# NAME_of_the_Game__NAND_Circuitry___Op-Am.net
KiCad netlist of a schematic drawn in EAGLE
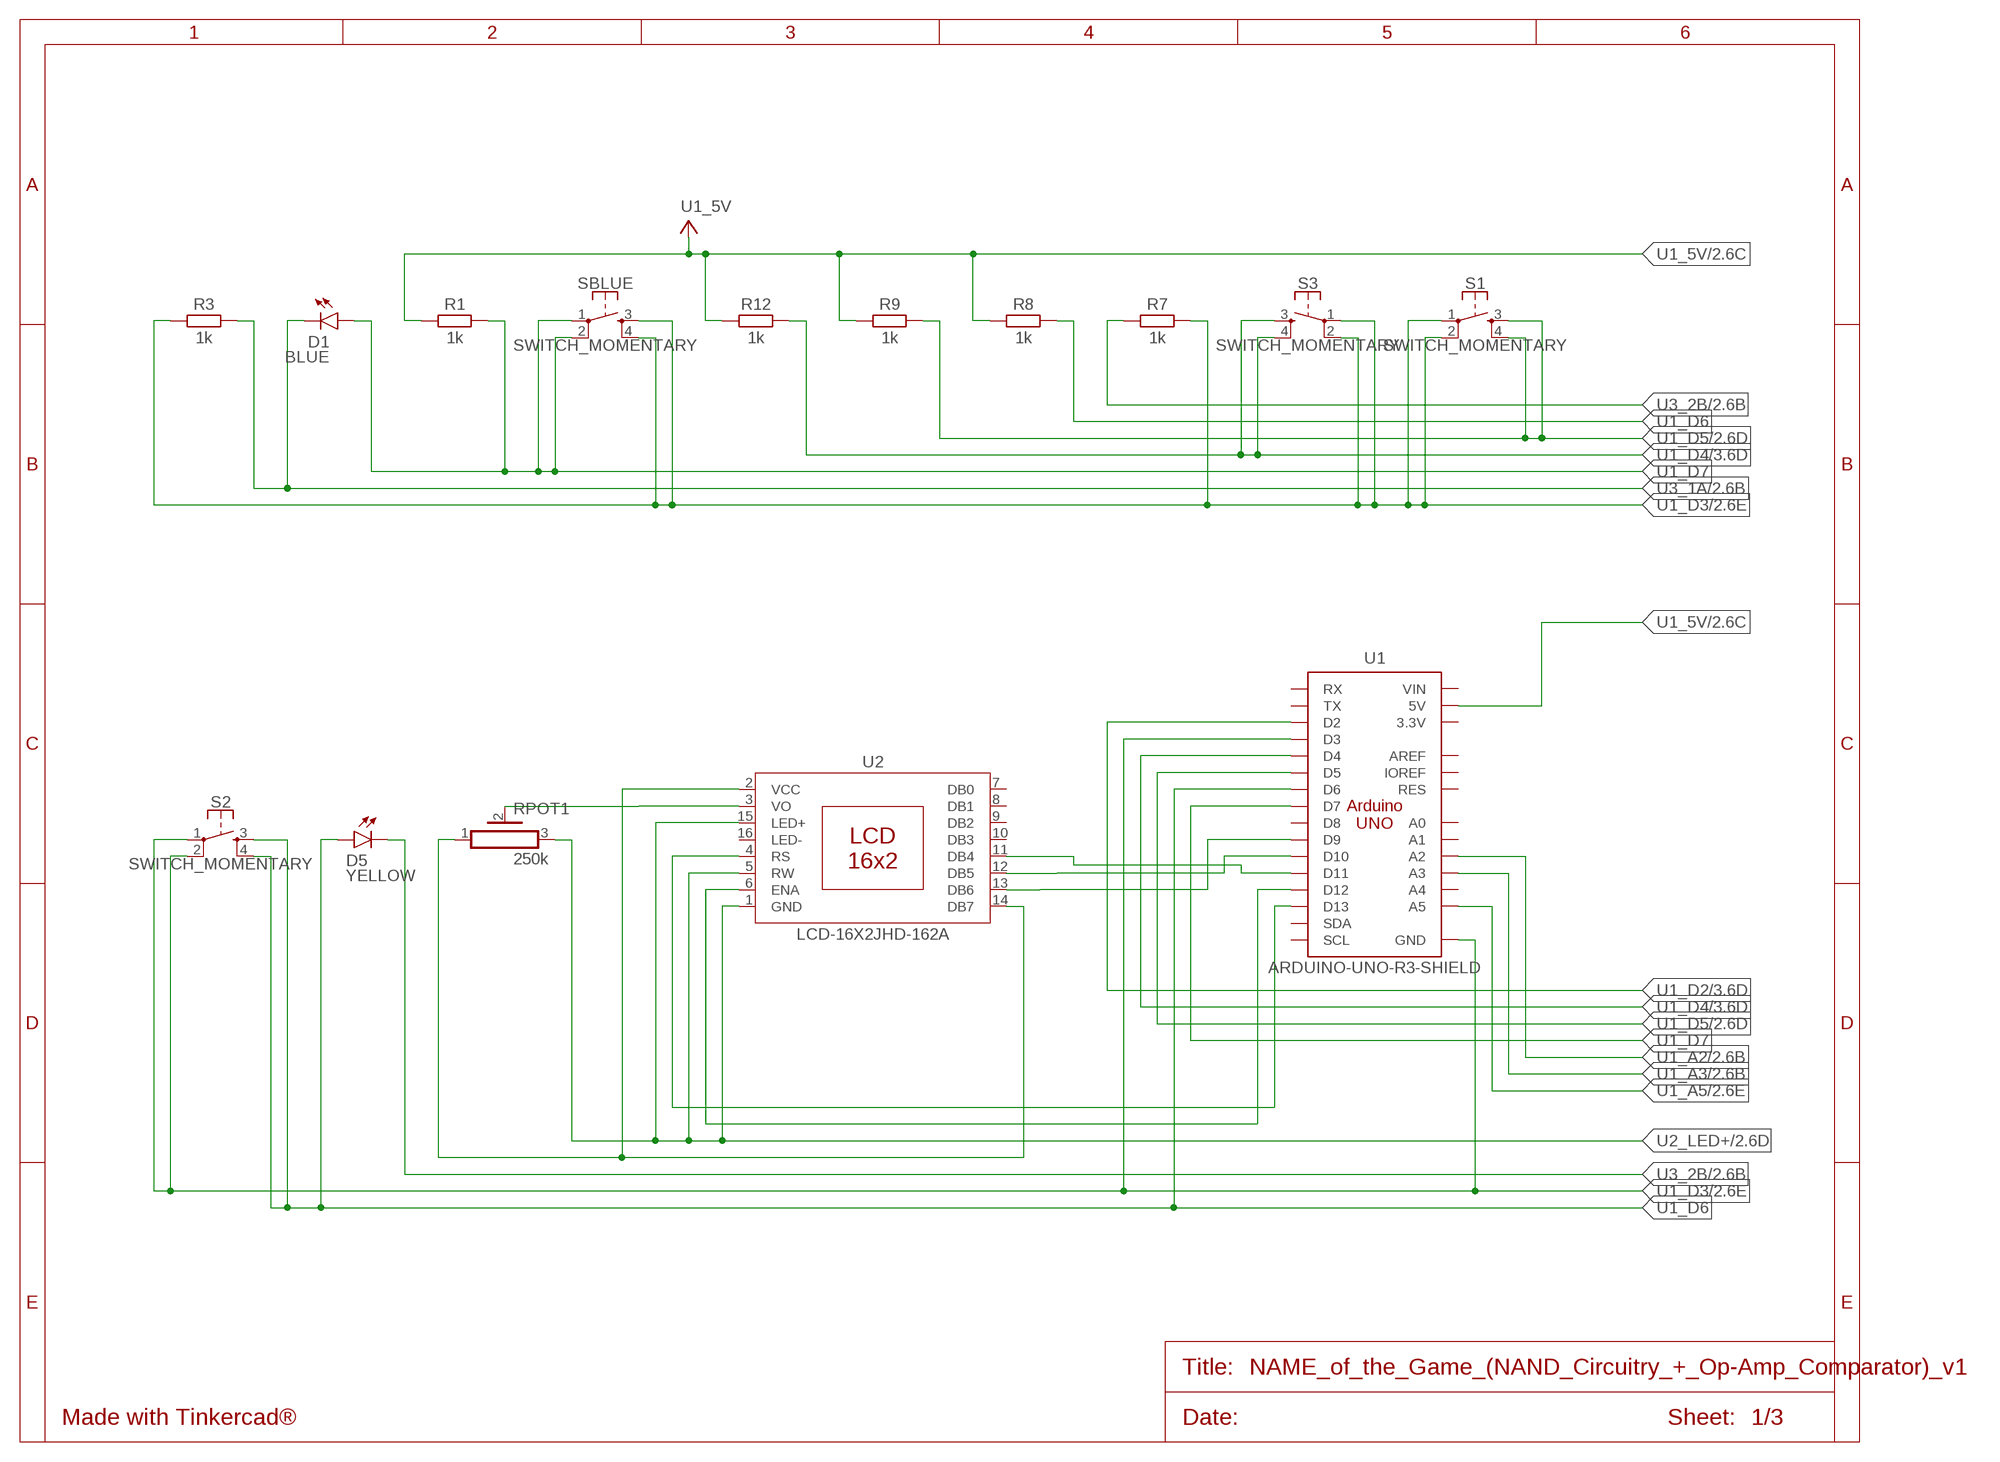
[diagram p0: schematic, sheet 1]
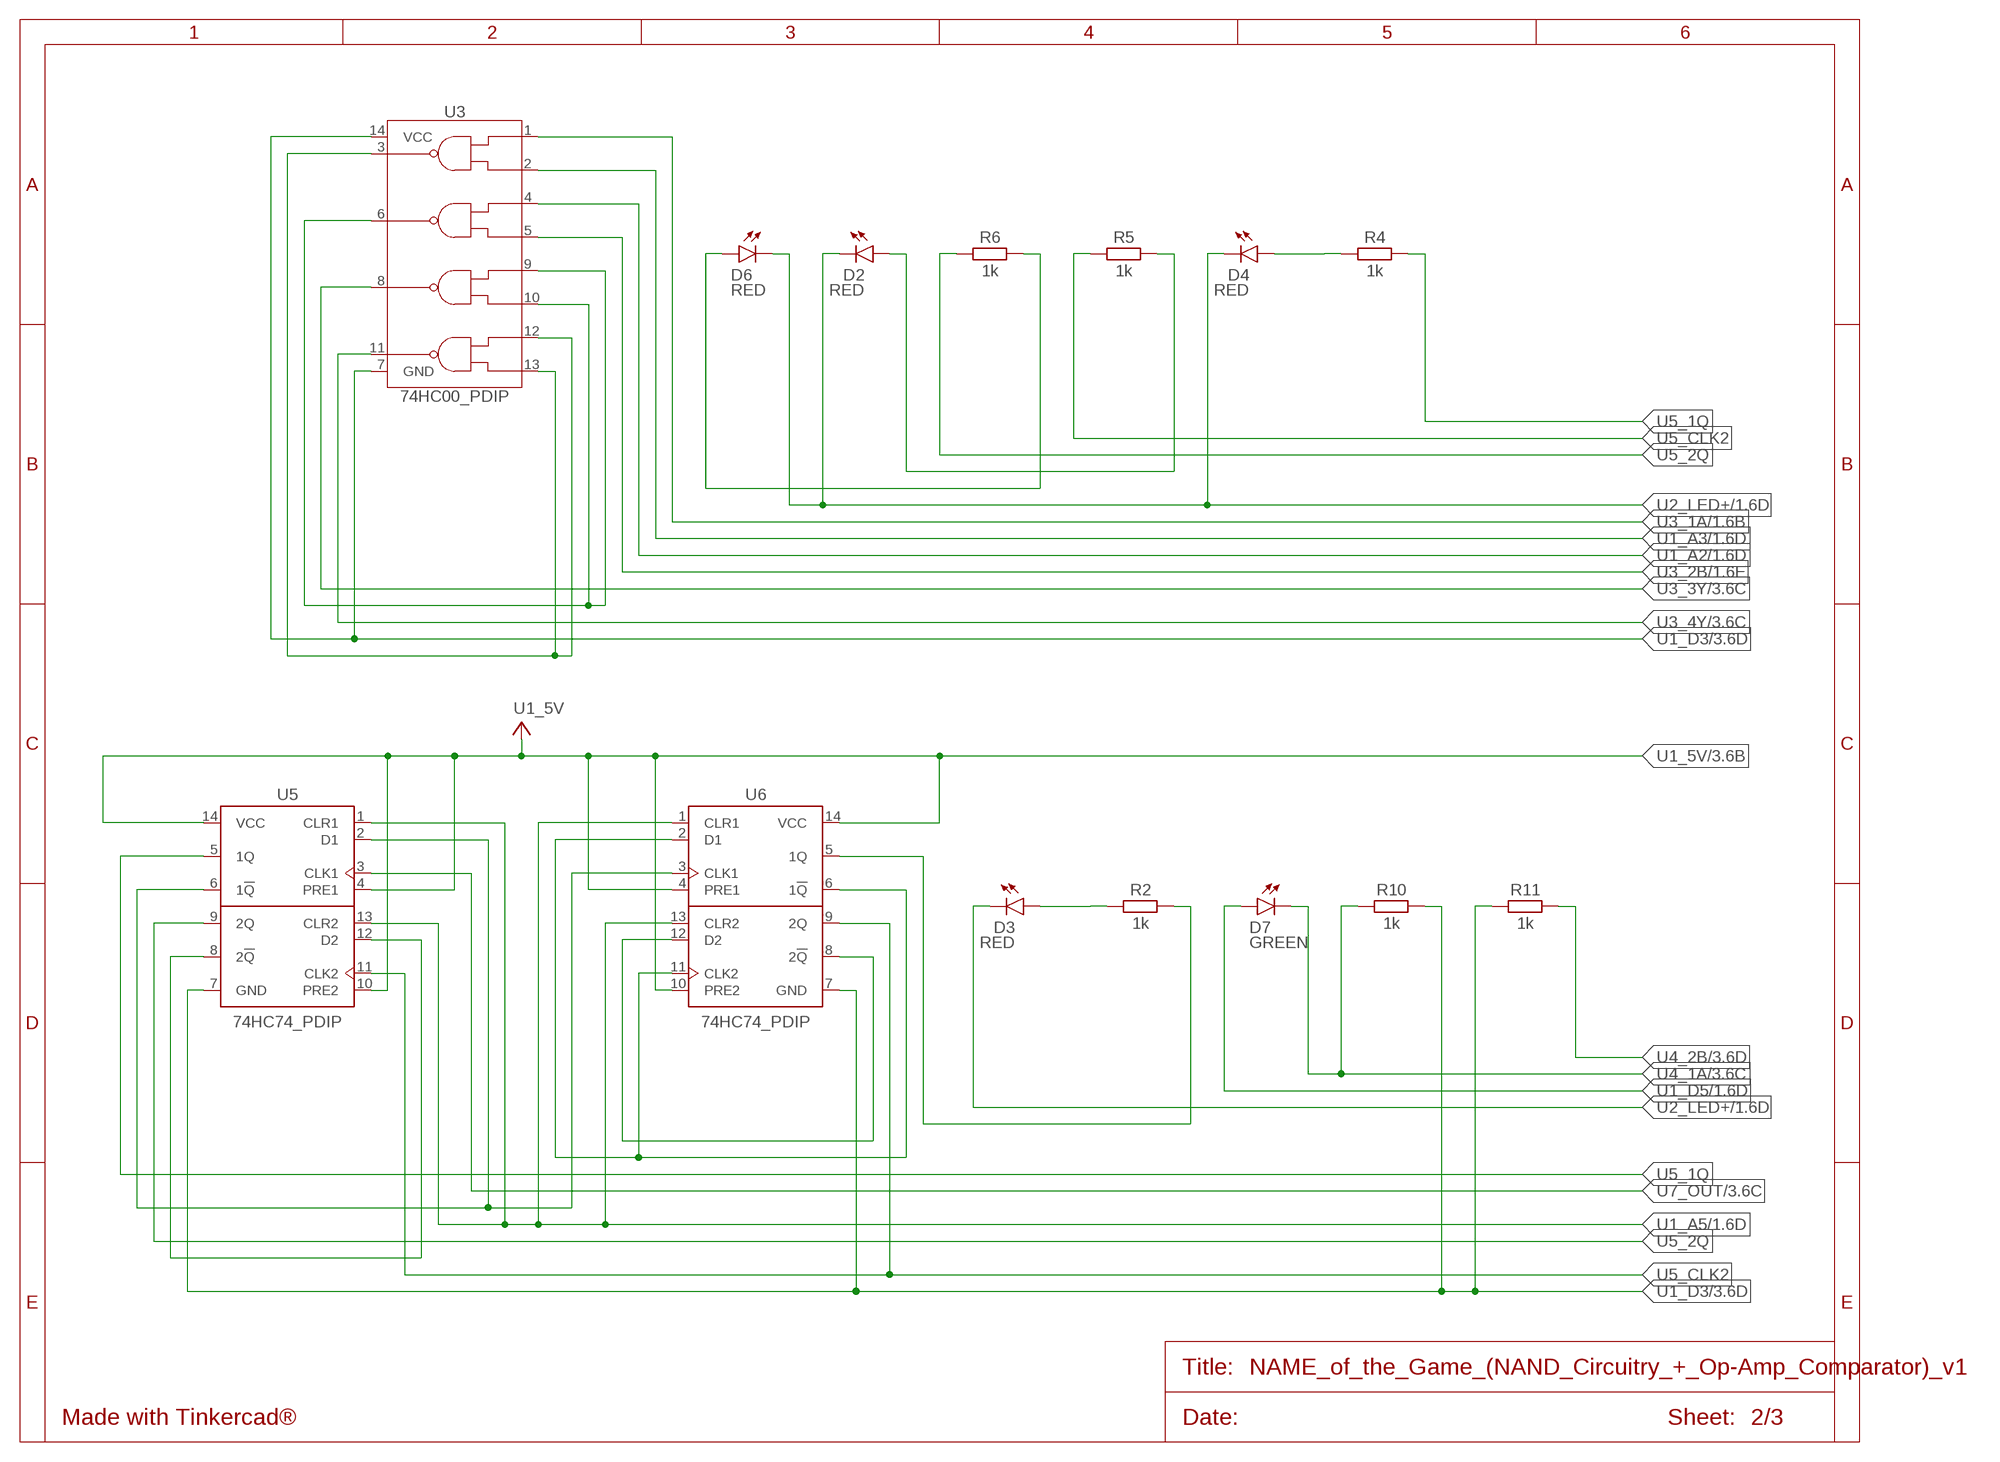
[diagram p1: schematic, sheet 2]
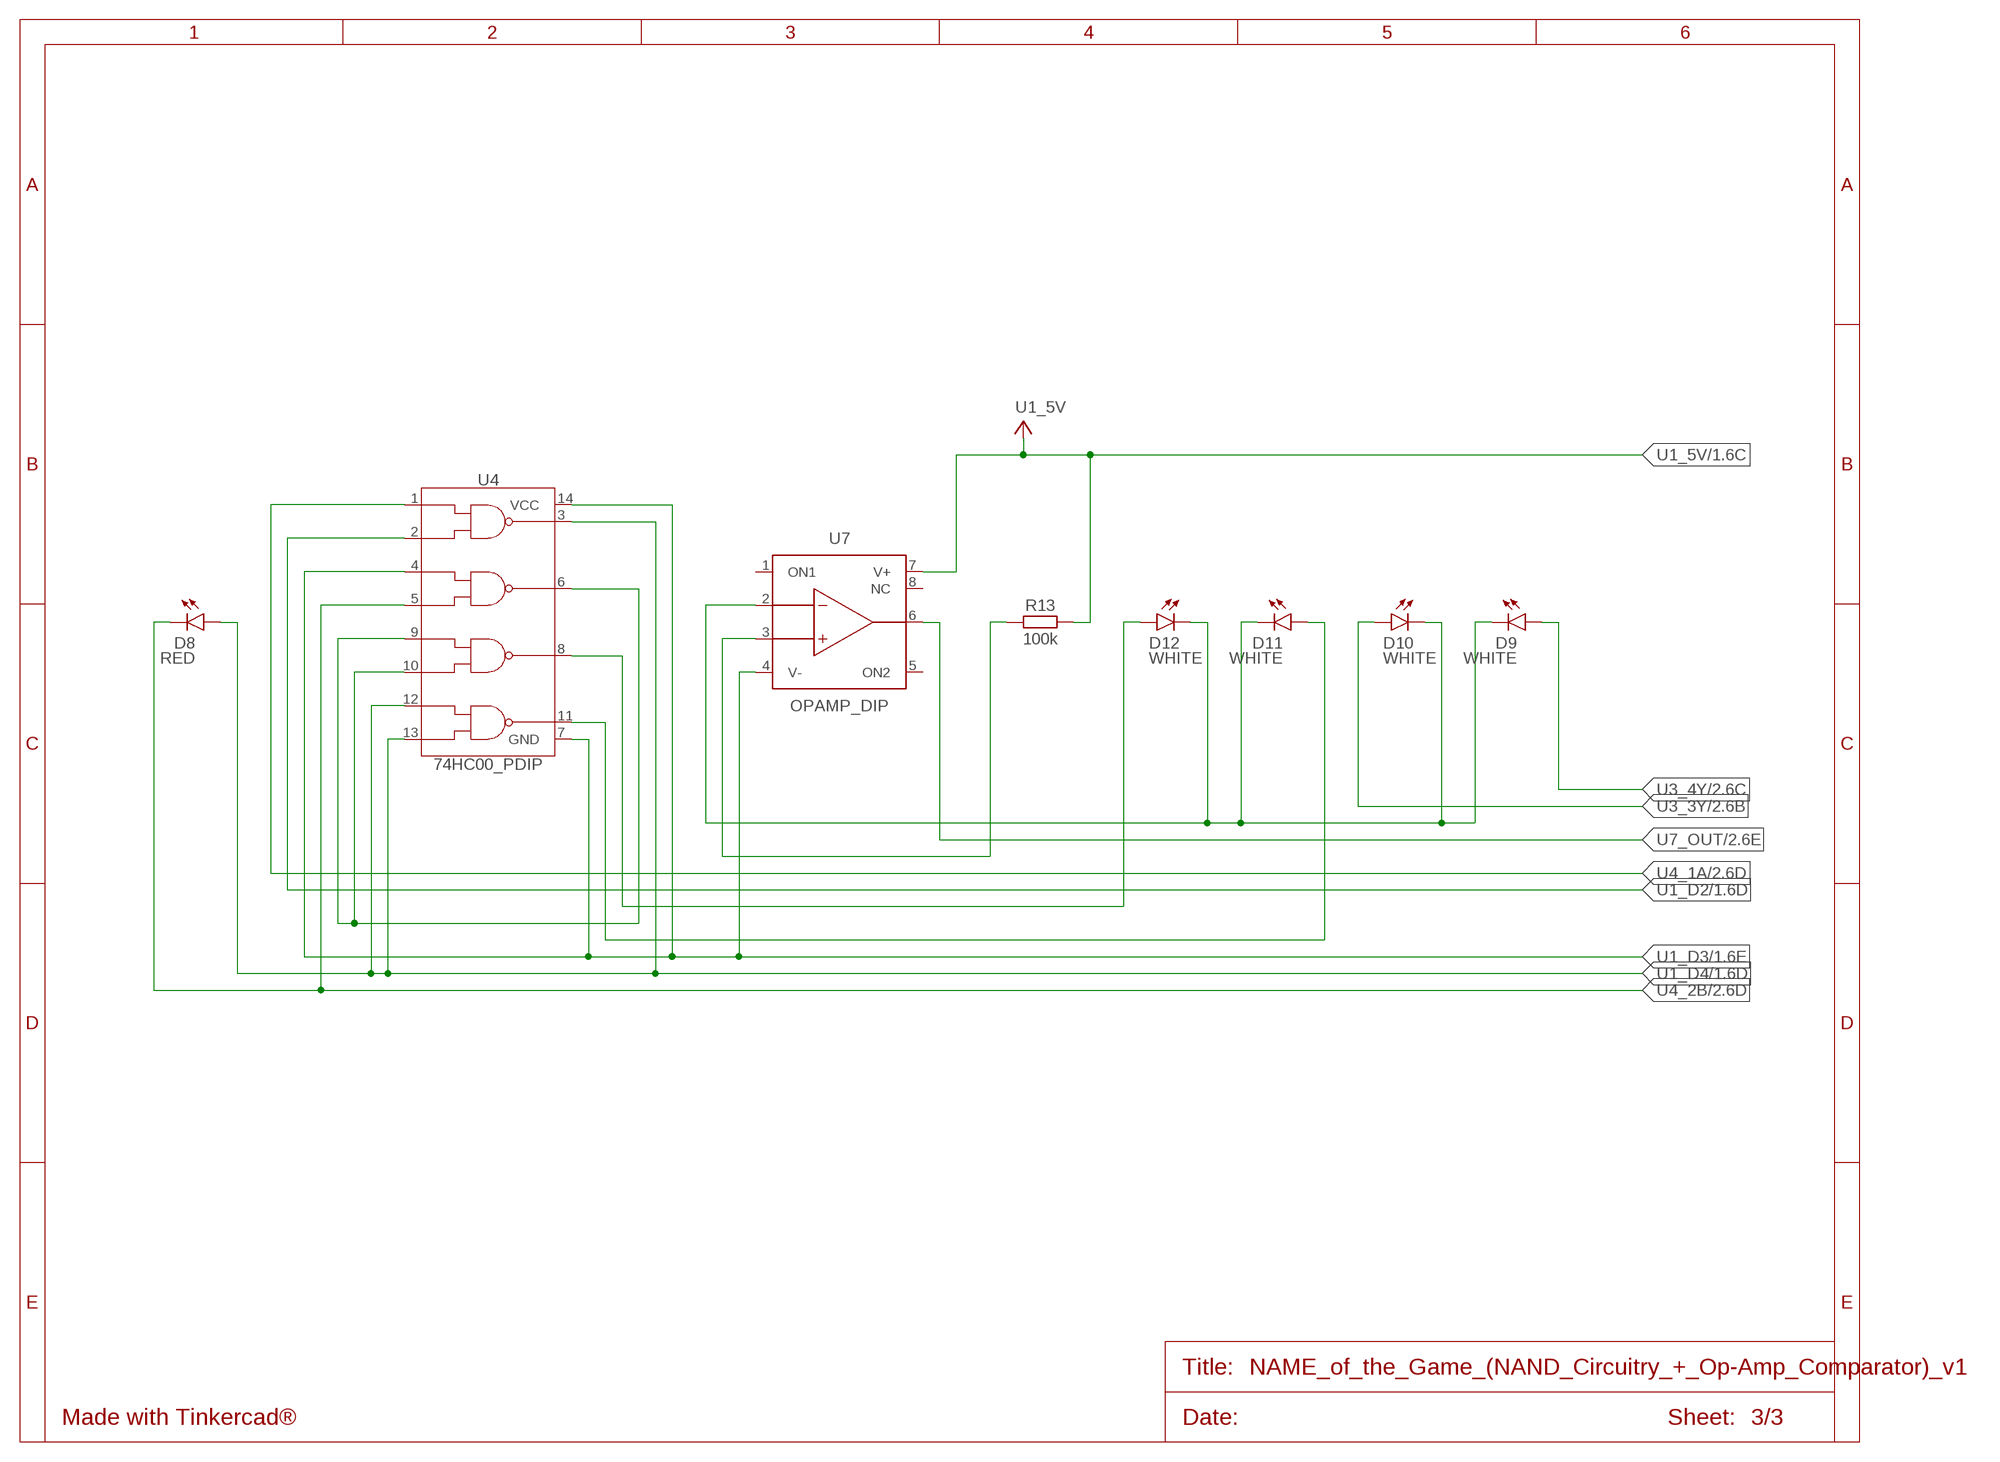
[diagram p2: schematic, sheet 3]

(export (version "E")
  (design (tool "Eeschema 10.0.6"))
  (components
    (comp (ref "D1")
      (value "BLUE")
      (footprint "eagle-import:LEDRD254W60D565H860B_B")
      (libsource (lib "eagle-import") (part "LED_RADIALBLUE_"))
    )
    (comp (ref "D5")
      (value "YELLOW")
      (footprint "eagle-import:LEDRD254W60D565H860B_Y")
      (libsource (lib "eagle-import") (part "LED_RADIALYELLOW_"))
    )
    (comp (ref "R1")
      (value "1k")
      (footprint "eagle-import:RESAD1016W63L850D250B")
      (libsource (lib "eagle-import") (part "RESISTOR_AXIAL-10.16MM-PITCH"))
    )
    (comp (ref "R3")
      (value "1k")
      (footprint "eagle-import:RESAD1016W63L850D250B")
      (libsource (lib "eagle-import") (part "RESISTOR_AXIAL-10.16MM-PITCH"))
    )
    (comp (ref "R7")
      (value "1k")
      (footprint "eagle-import:RESAD1016W63L850D250B")
      (libsource (lib "eagle-import") (part "RESISTOR_AXIAL-10.16MM-PITCH"))
    )
    (comp (ref "R8")
      (value "1k")
      (footprint "eagle-import:RESAD1016W63L850D250B")
      (libsource (lib "eagle-import") (part "RESISTOR_AXIAL-10.16MM-PITCH"))
    )
    (comp (ref "R9")
      (value "1k")
      (footprint "eagle-import:RESAD1016W63L850D250B")
      (libsource (lib "eagle-import") (part "RESISTOR_AXIAL-10.16MM-PITCH"))
    )
    (comp (ref "R12")
      (value "1k")
      (footprint "eagle-import:RESAD1016W63L850D250B")
      (libsource (lib "eagle-import") (part "RESISTOR_AXIAL-10.16MM-PITCH"))
    )
    (comp (ref "RPOT1")
      (value "250k")
      (footprint "eagle-import:HA-06-SM065")
      (libsource (lib "eagle-import") (part "POT_HA-06"))
    )
    (comp (ref "S1")
      (value "SWITCH_MOMENTARY")
      (footprint "eagle-import:SWITCH-MOMENTARY-PTH-6.5MM")
      (libsource (lib "eagle-import") (part "SWITCH_MOMENTARY"))
    )
    (comp (ref "S2")
      (value "SWITCH_MOMENTARY")
      (footprint "eagle-import:SWITCH-MOMENTARY-PTH-6.5MM")
      (libsource (lib "eagle-import") (part "SWITCH_MOMENTARY"))
    )
    (comp (ref "S3")
      (value "SWITCH_MOMENTARY")
      (footprint "eagle-import:SWITCH-MOMENTARY-PTH-6.5MM")
      (libsource (lib "eagle-import") (part "SWITCH_MOMENTARY"))
    )
    (comp (ref "SBLUE")
      (value "SWITCH_MOMENTARY")
      (footprint "eagle-import:SWITCH-MOMENTARY-PTH-6.5MM")
      (libsource (lib "eagle-import") (part "SWITCH_MOMENTARY"))
    )
    (comp (ref "U1")
      (value "ARDUINO-UNO-R3-SHIELD")
      (footprint "eagle-import:ARDUINO-UNO-R3-SHIELD")
      (libsource (lib "eagle-import") (part "ARDUINO-UNO-R3-SHIELD"))
    )
    (comp (ref "U2")
      (value "LCD-16X2JHD-162A")
      (footprint "eagle-import:JHD-162A")
      (libsource (lib "eagle-import") (part "LCD-16X2JHD-162A"))
    )
    (comp (ref "D2")
      (value "RED")
      (footprint "eagle-import:LEDRD254W60D565H860B")
      (libsource (lib "eagle-import") (part "LED_RADIALRED_"))
    )
    (comp (ref "D3")
      (value "RED")
      (footprint "eagle-import:LEDRD254W60D565H860B")
      (libsource (lib "eagle-import") (part "LED_RADIALRED_"))
    )
    (comp (ref "D4")
      (value "RED")
      (footprint "eagle-import:LEDRD254W60D565H860B")
      (libsource (lib "eagle-import") (part "LED_RADIALRED_"))
    )
    (comp (ref "D6")
      (value "RED")
      (footprint "eagle-import:LEDRD254W60D565H860B")
      (libsource (lib "eagle-import") (part "LED_RADIALRED_"))
    )
    (comp (ref "D7")
      (value "GREEN")
      (footprint "eagle-import:LEDRD254W60D565H860B_G")
      (libsource (lib "eagle-import") (part "LED_RADIALGREEN_"))
    )
    (comp (ref "R2")
      (value "1k")
      (footprint "eagle-import:RESAD1016W63L850D250B")
      (libsource (lib "eagle-import") (part "RESISTOR_AXIAL-10.16MM-PITCH"))
    )
    (comp (ref "R4")
      (value "1k")
      (footprint "eagle-import:RESAD1016W63L850D250B")
      (libsource (lib "eagle-import") (part "RESISTOR_AXIAL-10.16MM-PITCH"))
    )
    (comp (ref "R5")
      (value "1k")
      (footprint "eagle-import:RESAD1016W63L850D250B")
      (libsource (lib "eagle-import") (part "RESISTOR_AXIAL-10.16MM-PITCH"))
    )
    (comp (ref "R6")
      (value "1k")
      (footprint "eagle-import:RESAD1016W63L850D250B")
      (libsource (lib "eagle-import") (part "RESISTOR_AXIAL-10.16MM-PITCH"))
    )
    (comp (ref "R10")
      (value "1k")
      (footprint "eagle-import:RESAD1016W63L850D250B")
      (libsource (lib "eagle-import") (part "RESISTOR_AXIAL-10.16MM-PITCH"))
    )
    (comp (ref "R11")
      (value "1k")
      (footprint "eagle-import:RESAD1016W63L850D250B")
      (libsource (lib "eagle-import") (part "RESISTOR_AXIAL-10.16MM-PITCH"))
    )
    (comp (ref "U3")
      (value "74HC00_PDIP")
      (footprint "eagle-import:DIP762W53P254L1969H508Q14B")
      (libsource (lib "eagle-import") (part "74HC00_PDIP"))
    )
    (comp (ref "U5")
      (value "74HC74_PDIP")
      (footprint "eagle-import:DIP762W53P254L1969H508Q14B")
      (libsource (lib "eagle-import") (part "74HC74_PDIP"))
    )
    (comp (ref "U6")
      (value "74HC74_PDIP")
      (footprint "eagle-import:DIP762W53P254L1969H508Q14B")
      (libsource (lib "eagle-import") (part "74HC74_PDIP"))
    )
    (comp (ref "D8")
      (value "RED")
      (footprint "eagle-import:LEDRD254W60D565H860B")
      (libsource (lib "eagle-import") (part "LED_RADIALRED_"))
    )
    (comp (ref "D9")
      (value "WHITE")
      (footprint "eagle-import:LEDRD254W60D565H860B_W")
      (libsource (lib "eagle-import") (part "LED_RADIALWHITE_"))
    )
    (comp (ref "D10")
      (value "WHITE")
      (footprint "eagle-import:LEDRD254W60D565H860B_W")
      (libsource (lib "eagle-import") (part "LED_RADIALWHITE_"))
    )
    (comp (ref "D11")
      (value "WHITE")
      (footprint "eagle-import:LEDRD254W60D565H860B_W")
      (libsource (lib "eagle-import") (part "LED_RADIALWHITE_"))
    )
    (comp (ref "D12")
      (value "WHITE")
      (footprint "eagle-import:LEDRD254W60D565H860B_W")
      (libsource (lib "eagle-import") (part "LED_RADIALWHITE_"))
    )
    (comp (ref "R13")
      (value "100k")
      (footprint "eagle-import:RESAD1016W63L850D250B")
      (libsource (lib "eagle-import") (part "RESISTOR_AXIAL-10.16MM-PITCH"))
    )
    (comp (ref "U4")
      (value "74HC00_PDIP")
      (footprint "eagle-import:DIP762W53P254L1969H508Q14B")
      (libsource (lib "eagle-import") (part "74HC00_PDIP"))
    )
    (comp (ref "U7")
      (value "OPAMP_DIP")
      (footprint "eagle-import:DIP826W53P254L959H508Q8B")
      (libsource (lib "eagle-import") (part "OPAMP_DIP"))
    )
  )
  (nets
    (net (code "1") (name "Net-(D2-A)") (class "Default")
      (node (ref "D2") (pin "1") (pinfunction "A_1") (pintype "passive"))
      (node (ref "R5") (pin "2") (pinfunction "2_2") (pintype "passive"))
    )
    (net (code "2") (name "Net-(D3-A)") (class "Default")
      (node (ref "D3") (pin "1") (pinfunction "A_1") (pintype "passive"))
      (node (ref "R2") (pin "2") (pinfunction "2_2") (pintype "passive"))
    )
    (net (code "3") (name "Net-(D4-A)") (class "Default")
      (node (ref "D4") (pin "1") (pinfunction "A_1") (pintype "passive"))
      (node (ref "R4") (pin "2") (pinfunction "2_2") (pintype "passive"))
    )
    (net (code "4") (name "Net-(D6-A)") (class "Default")
      (node (ref "D6") (pin "1") (pinfunction "A_1") (pintype "passive"))
      (node (ref "R6") (pin "2") (pinfunction "2_2") (pintype "passive"))
    )
    (net (code "5") (name "Net-(D10-C)") (class "Default")
      (node (ref "D10") (pin "2") (pinfunction "C_2") (pintype "passive"))
      (node (ref "D11") (pin "2") (pinfunction "C_2") (pintype "passive"))
      (node (ref "D12") (pin "2") (pinfunction "C_2") (pintype "passive"))
      (node (ref "D9") (pin "2") (pinfunction "C_2") (pintype "passive"))
      (node (ref "U7") (pin "2") (pinfunction "-IN_2") (pintype "input"))
    )
    (net (code "6") (name "Net-(D11-A)") (class "Default")
      (node (ref "D11") (pin "1") (pinfunction "A_1") (pintype "passive"))
      (node (ref "U4") (pin "11") (pinfunction "4Y_11") (pintype "output"))
    )
    (net (code "7") (name "Net-(D12-A)") (class "Default")
      (node (ref "D12") (pin "1") (pinfunction "A_1") (pintype "passive"))
      (node (ref "U4") (pin "8") (pinfunction "3Y_8") (pintype "output"))
    )
    (net (code "8") (name "Net-(RPOT1-P$1)") (class "Default")
      (node (ref "RPOT1") (pin "1") (pinfunction "P$1_1") (pintype "passive"))
      (node (ref "U2") (pin "14") (pinfunction "DB7_14") (pintype "bidirectional"))
      (node (ref "U2") (pin "2") (pinfunction "VCC_2") (pintype "bidirectional"))
    )
    (net (code "9") (name "Net-(RPOT1-P$2)") (class "Default")
      (node (ref "RPOT1") (pin "2") (pinfunction "P$2_2") (pintype "passive"))
      (node (ref "U2") (pin "3") (pinfunction "VO_3") (pintype "bidirectional"))
    )
    (net (code "10") (name "Net-(U2-DB4)") (class "Default")
      (node (ref "U1") (pin "D11") (pinfunction "D11_D11") (pintype "bidirectional"))
      (node (ref "U2") (pin "11") (pinfunction "DB4_11") (pintype "bidirectional"))
    )
    (net (code "11") (name "Net-(U2-DB5)") (class "Default")
      (node (ref "U1") (pin "D10") (pinfunction "D10_D10") (pintype "bidirectional"))
      (node (ref "U2") (pin "12") (pinfunction "DB5_12") (pintype "bidirectional"))
    )
    (net (code "12") (name "Net-(U2-DB6)") (class "Default")
      (node (ref "U1") (pin "D9") (pinfunction "D9_D9") (pintype "bidirectional"))
      (node (ref "U2") (pin "13") (pinfunction "DB6_13") (pintype "bidirectional"))
    )
    (net (code "13") (name "Net-(U2-ENA)") (class "Default")
      (node (ref "U1") (pin "D12") (pinfunction "D12_D12") (pintype "bidirectional"))
      (node (ref "U2") (pin "6") (pinfunction "ENA_6") (pintype "bidirectional"))
    )
    (net (code "14") (name "Net-(U2-RS)") (class "Default")
      (node (ref "U1") (pin "D13") (pinfunction "D13_D13") (pintype "bidirectional"))
      (node (ref "U2") (pin "4") (pinfunction "RS_4") (pintype "bidirectional"))
    )
    (net (code "15") (name "Net-(U3-1Y)") (class "Default")
      (node (ref "U3") (pin "12") (pinfunction "4A_12") (pintype "input"))
      (node (ref "U3") (pin "13") (pinfunction "4B_13") (pintype "input"))
      (node (ref "U3") (pin "3") (pinfunction "1Y_3") (pintype "output"))
    )
    (net (code "16") (name "Net-(U3-2Y)") (class "Default")
      (node (ref "U3") (pin "10") (pinfunction "3B_10") (pintype "input"))
      (node (ref "U3") (pin "6") (pinfunction "2Y_6") (pintype "output"))
      (node (ref "U3") (pin "9") (pinfunction "3A_9") (pintype "input"))
    )
    (net (code "17") (name "Net-(U4-2Y)") (class "Default")
      (node (ref "U4") (pin "10") (pinfunction "3B_10") (pintype "input"))
      (node (ref "U4") (pin "6") (pinfunction "2Y_6") (pintype "output"))
      (node (ref "U4") (pin "9") (pinfunction "3A_9") (pintype "input"))
    )
    (net (code "18") (name "Net-(U5-1~{Q})") (class "Default")
      (node (ref "U5") (pin "2") (pinfunction "D1_2") (pintype "input"))
      (node (ref "U5") (pin "6") (pinfunction "1~{Q}_6") (pintype "output"))
      (node (ref "U6") (pin "3") (pinfunction "CLK1_3") (pintype "input"))
    )
    (net (code "19") (name "Net-(U5-2~{Q})") (class "Default")
      (node (ref "U5") (pin "12") (pinfunction "D2_12") (pintype "input"))
      (node (ref "U5") (pin "8") (pinfunction "2~{Q}_8") (pintype "output"))
    )
    (net (code "20") (name "Net-(U6-1Q)") (class "Default")
      (node (ref "R2") (pin "1") (pinfunction "1_1") (pintype "passive"))
      (node (ref "U6") (pin "5") (pinfunction "1Q_5") (pintype "output"))
    )
    (net (code "21") (name "Net-(U6-1~{Q})") (class "Default")
      (node (ref "U6") (pin "11") (pinfunction "CLK2_11") (pintype "input"))
      (node (ref "U6") (pin "2") (pinfunction "D1_2") (pintype "input"))
      (node (ref "U6") (pin "6") (pinfunction "1~{Q}_6") (pintype "output"))
    )
    (net (code "22") (name "Net-(U6-2~{Q})") (class "Default")
      (node (ref "U6") (pin "12") (pinfunction "D2_12") (pintype "input"))
      (node (ref "U6") (pin "8") (pinfunction "2~{Q}_8") (pintype "output"))
    )
    (net (code "23") (name "Net-(U7-+IN)") (class "Default")
      (node (ref "R13") (pin "2") (pinfunction "2_2") (pintype "passive"))
      (node (ref "U7") (pin "3") (pinfunction "+IN_3") (pintype "input"))
    )
    (net (code "24") (name "U1_5V") (class "Default")
      (node (ref "R1") (pin "1") (pinfunction "1_1") (pintype "passive"))
      (node (ref "R12") (pin "1") (pinfunction "1_1") (pintype "passive"))
      (node (ref "R13") (pin "1") (pinfunction "1_1") (pintype "passive"))
      (node (ref "R8") (pin "1") (pinfunction "1_1") (pintype "passive"))
      (node (ref "R9") (pin "1") (pinfunction "1_1") (pintype "passive"))
      (node (ref "U1") (pin "5V") (pinfunction "5V_5V") (pintype "bidirectional"))
      (node (ref "U5") (pin "10") (pinfunction "PRE2_10") (pintype "input"))
      (node (ref "U5") (pin "14") (pinfunction "VCC_14") (pintype "bidirectional"))
      (node (ref "U5") (pin "4") (pinfunction "PRE1_4") (pintype "input"))
      (node (ref "U6") (pin "10") (pinfunction "PRE2_10") (pintype "input"))
      (node (ref "U6") (pin "14") (pinfunction "VCC_14") (pintype "bidirectional"))
      (node (ref "U6") (pin "4") (pinfunction "PRE1_4") (pintype "input"))
      (node (ref "U7") (pin "7") (pinfunction "V+_7") (pintype "bidirectional"))
    )
    (net (code "25") (name "U1_A2") (class "Default")
      (node (ref "U1") (pin "A2") (pinfunction "A2_A2") (pintype "bidirectional"))
      (node (ref "U3") (pin "4") (pinfunction "2A_4") (pintype "input"))
    )
    (net (code "26") (name "U1_A3") (class "Default")
      (node (ref "U1") (pin "A3") (pinfunction "A3_A3") (pintype "bidirectional"))
      (node (ref "U3") (pin "2") (pinfunction "1B_2") (pintype "input"))
    )
    (net (code "27") (name "U1_A5") (class "Default")
      (node (ref "U1") (pin "A5") (pinfunction "A5_A5") (pintype "bidirectional"))
      (node (ref "U5") (pin "1") (pinfunction "CLR1_1") (pintype "input"))
      (node (ref "U5") (pin "13") (pinfunction "CLR2_13") (pintype "input"))
      (node (ref "U6") (pin "1") (pinfunction "CLR1_1") (pintype "input"))
      (node (ref "U6") (pin "13") (pinfunction "CLR2_13") (pintype "input"))
    )
    (net (code "28") (name "U1_D2") (class "Default")
      (node (ref "U1") (pin "D2") (pinfunction "D2_D2") (pintype "bidirectional"))
      (node (ref "U4") (pin "2") (pinfunction "1B_2") (pintype "input"))
    )
    (net (code "29") (name "U1_D3") (class "Default")
      (node (ref "R10") (pin "2") (pinfunction "2_2") (pintype "passive"))
      (node (ref "R11") (pin "2") (pinfunction "2_2") (pintype "passive"))
      (node (ref "R3") (pin "2") (pinfunction "2_2") (pintype "passive"))
      (node (ref "R7") (pin "2") (pinfunction "2_2") (pintype "passive"))
      (node (ref "S1") (pin "1") (pinfunction "1_1") (pintype "passive"))
      (node (ref "S1") (pin "2") (pinfunction "2_2") (pintype "passive"))
      (node (ref "S2") (pin "1") (pinfunction "1_1") (pintype "passive"))
      (node (ref "S2") (pin "2") (pinfunction "2_2") (pintype "passive"))
      (node (ref "S3") (pin "1") (pinfunction "1_1") (pintype "passive"))
      (node (ref "S3") (pin "2") (pinfunction "2_2") (pintype "passive"))
      (node (ref "SBLUE") (pin "3") (pinfunction "3_3") (pintype "passive"))
      (node (ref "SBLUE") (pin "4") (pinfunction "4_4") (pintype "passive"))
      (node (ref "U1") (pin "D3") (pinfunction "D3_D3") (pintype "bidirectional"))
      (node (ref "U1") (pin "GND@0") (pinfunction "GND_GND@0") (pintype "bidirectional"))
      (node (ref "U1") (pin "GND@1") (pinfunction "GND_GND@1") (pintype "bidirectional"))
      (node (ref "U1") (pin "GND@2") (pinfunction "GND_GND@2") (pintype "bidirectional"))
      (node (ref "U3") (pin "14") (pinfunction "VCC_14") (pintype "bidirectional"))
      (node (ref "U3") (pin "7") (pinfunction "GND_7") (pintype "bidirectional"))
      (node (ref "U4") (pin "14") (pinfunction "VCC_14") (pintype "bidirectional"))
      (node (ref "U4") (pin "4") (pinfunction "2A_4") (pintype "input"))
      (node (ref "U4") (pin "7") (pinfunction "GND_7") (pintype "bidirectional"))
      (node (ref "U5") (pin "7") (pinfunction "GND_7") (pintype "bidirectional"))
      (node (ref "U6") (pin "7") (pinfunction "GND_7") (pintype "bidirectional"))
      (node (ref "U7") (pin "4") (pinfunction "V-_4") (pintype "bidirectional"))
    )
    (net (code "30") (name "U1_D4") (class "Default")
      (node (ref "D8") (pin "1") (pinfunction "A_1") (pintype "passive"))
      (node (ref "R12") (pin "2") (pinfunction "2_2") (pintype "passive"))
      (node (ref "S3") (pin "3") (pinfunction "3_3") (pintype "passive"))
      (node (ref "S3") (pin "4") (pinfunction "4_4") (pintype "passive"))
      (node (ref "U1") (pin "D4") (pinfunction "D4_D4") (pintype "bidirectional"))
      (node (ref "U4") (pin "12") (pinfunction "4A_12") (pintype "input"))
      (node (ref "U4") (pin "13") (pinfunction "4B_13") (pintype "input"))
      (node (ref "U4") (pin "3") (pinfunction "1Y_3") (pintype "output"))
    )
    (net (code "31") (name "U1_D5") (class "Default")
      (node (ref "D7") (pin "1") (pinfunction "A_1") (pintype "passive"))
      (node (ref "R9") (pin "2") (pinfunction "2_2") (pintype "passive"))
      (node (ref "S1") (pin "3") (pinfunction "3_3") (pintype "passive"))
      (node (ref "S1") (pin "4") (pinfunction "4_4") (pintype "passive"))
      (node (ref "U1") (pin "D5") (pinfunction "D5_D5") (pintype "bidirectional"))
    )
    (net (code "32") (name "U1_D6") (class "Default")
      (node (ref "D5") (pin "1") (pinfunction "A_1") (pintype "passive"))
      (node (ref "R8") (pin "2") (pinfunction "2_2") (pintype "passive"))
      (node (ref "S2") (pin "3") (pinfunction "3_3") (pintype "passive"))
      (node (ref "S2") (pin "4") (pinfunction "4_4") (pintype "passive"))
      (node (ref "U1") (pin "D6") (pinfunction "D6_D6") (pintype "bidirectional"))
    )
    (net (code "33") (name "U1_D7") (class "Default")
      (node (ref "D1") (pin "1") (pinfunction "A_1") (pintype "passive"))
      (node (ref "R1") (pin "2") (pinfunction "2_2") (pintype "passive"))
      (node (ref "SBLUE") (pin "1") (pinfunction "1_1") (pintype "passive"))
      (node (ref "SBLUE") (pin "2") (pinfunction "2_2") (pintype "passive"))
      (node (ref "U1") (pin "D7") (pinfunction "D7_D7") (pintype "bidirectional"))
    )
    (net (code "34") (name "U2_LED+") (class "Default")
      (node (ref "D2") (pin "2") (pinfunction "C_2") (pintype "passive"))
      (node (ref "D3") (pin "2") (pinfunction "C_2") (pintype "passive"))
      (node (ref "D4") (pin "2") (pinfunction "C_2") (pintype "passive"))
      (node (ref "D6") (pin "2") (pinfunction "C_2") (pintype "passive"))
      (node (ref "RPOT1") (pin "3") (pinfunction "P$3_3") (pintype "passive"))
      (node (ref "U2") (pin "1") (pinfunction "GND_1") (pintype "bidirectional"))
      (node (ref "U2") (pin "15") (pinfunction "LED+_15") (pintype "bidirectional"))
      (node (ref "U2") (pin "5") (pinfunction "RW_5") (pintype "bidirectional"))
    )
    (net (code "35") (name "U3_1A") (class "Default")
      (node (ref "D1") (pin "2") (pinfunction "C_2") (pintype "passive"))
      (node (ref "R3") (pin "1") (pinfunction "1_1") (pintype "passive"))
      (node (ref "U3") (pin "1") (pinfunction "1A_1") (pintype "input"))
    )
    (net (code "36") (name "U3_2B") (class "Default")
      (node (ref "D5") (pin "2") (pinfunction "C_2") (pintype "passive"))
      (node (ref "R7") (pin "1") (pinfunction "1_1") (pintype "passive"))
      (node (ref "U3") (pin "5") (pinfunction "2B_5") (pintype "input"))
    )
    (net (code "37") (name "U3_3Y") (class "Default")
      (node (ref "D10") (pin "1") (pinfunction "A_1") (pintype "passive"))
      (node (ref "U3") (pin "8") (pinfunction "3Y_8") (pintype "output"))
    )
    (net (code "38") (name "U3_4Y") (class "Default")
      (node (ref "D9") (pin "1") (pinfunction "A_1") (pintype "passive"))
      (node (ref "U3") (pin "11") (pinfunction "4Y_11") (pintype "output"))
    )
    (net (code "39") (name "U4_1A") (class "Default")
      (node (ref "D7") (pin "2") (pinfunction "C_2") (pintype "passive"))
      (node (ref "R10") (pin "1") (pinfunction "1_1") (pintype "passive"))
      (node (ref "U4") (pin "1") (pinfunction "1A_1") (pintype "input"))
    )
    (net (code "40") (name "U4_2B") (class "Default")
      (node (ref "D8") (pin "2") (pinfunction "C_2") (pintype "passive"))
      (node (ref "R11") (pin "1") (pinfunction "1_1") (pintype "passive"))
      (node (ref "U4") (pin "5") (pinfunction "2B_5") (pintype "input"))
    )
    (net (code "41") (name "U5_1Q") (class "Default")
      (node (ref "R4") (pin "1") (pinfunction "1_1") (pintype "passive"))
      (node (ref "U5") (pin "5") (pinfunction "1Q_5") (pintype "output"))
    )
    (net (code "42") (name "U5_2Q") (class "Default")
      (node (ref "R6") (pin "1") (pinfunction "1_1") (pintype "passive"))
      (node (ref "U5") (pin "9") (pinfunction "2Q_9") (pintype "output"))
    )
    (net (code "43") (name "U5_CLK2") (class "Default")
      (node (ref "R5") (pin "1") (pinfunction "1_1") (pintype "passive"))
      (node (ref "U5") (pin "11") (pinfunction "CLK2_11") (pintype "input"))
      (node (ref "U6") (pin "9") (pinfunction "2Q_9") (pintype "output"))
    )
    (net (code "44") (name "U7_OUT") (class "Default")
      (node (ref "U5") (pin "3") (pinfunction "CLK1_3") (pintype "input"))
      (node (ref "U7") (pin "6") (pinfunction "OUT_6") (pintype "output"))
    )
    (net (code "45") (name "unconnected-(U1-Pad3.3V)") (class "Default")
      (node (ref "U1") (pin "3.3V") (pinfunction "3.3V_3.3V") (pintype "bidirectional"))
    )
    (net (code "46") (name "unconnected-(U1-PadA0)") (class "Default")
      (node (ref "U1") (pin "A0") (pinfunction "A0_A0") (pintype "bidirectional"))
    )
    (net (code "47") (name "unconnected-(U1-PadA1)") (class "Default")
      (node (ref "U1") (pin "A1") (pinfunction "A1_A1") (pintype "bidirectional"))
    )
    (net (code "48") (name "unconnected-(U1-PadA4)") (class "Default")
      (node (ref "U1") (pin "A4") (pinfunction "A4_A4") (pintype "bidirectional"))
    )
    (net (code "49") (name "unconnected-(U1-PadAREF)") (class "Default")
      (node (ref "U1") (pin "AREF") (pinfunction "AREF_AREF") (pintype "bidirectional"))
    )
    (net (code "50") (name "unconnected-(U1-PadD8)") (class "Default")
      (node (ref "U1") (pin "D8") (pinfunction "D8_D8") (pintype "bidirectional"))
    )
    (net (code "51") (name "unconnected-(U1-PadIOREF)") (class "Default")
      (node (ref "U1") (pin "IOREF") (pinfunction "IOREF_IOREF") (pintype "bidirectional"))
    )
    (net (code "52") (name "unconnected-(U1-PadRES)") (class "Default")
      (node (ref "U1") (pin "RES") (pinfunction "RES_RES") (pintype "bidirectional"))
    )
    (net (code "53") (name "unconnected-(U1-PadRX)") (class "Default")
      (node (ref "U1") (pin "RX") (pinfunction "RX_RX") (pintype "bidirectional"))
    )
    (net (code "54") (name "unconnected-(U1-PadSCL)") (class "Default")
      (node (ref "U1") (pin "SCL") (pinfunction "SCL_SCL") (pintype "bidirectional"))
    )
    (net (code "55") (name "unconnected-(U1-PadSDA)") (class "Default")
      (node (ref "U1") (pin "SDA") (pinfunction "SDA_SDA") (pintype "bidirectional"))
    )
    (net (code "56") (name "unconnected-(U1-PadTX)") (class "Default")
      (node (ref "U1") (pin "TX") (pinfunction "TX_TX") (pintype "bidirectional"))
    )
    (net (code "57") (name "unconnected-(U1-PadVIN)") (class "Default")
      (node (ref "U1") (pin "VIN") (pinfunction "VIN_VIN") (pintype "bidirectional"))
    )
    (net (code "58") (name "unconnected-(U2-DB0-Pad7)") (class "Default")
      (node (ref "U2") (pin "7") (pinfunction "DB0_7") (pintype "bidirectional"))
    )
    (net (code "59") (name "unconnected-(U2-DB1-Pad8)") (class "Default")
      (node (ref "U2") (pin "8") (pinfunction "DB1_8") (pintype "bidirectional"))
    )
    (net (code "60") (name "unconnected-(U2-DB2-Pad9)") (class "Default")
      (node (ref "U2") (pin "9") (pinfunction "DB2_9") (pintype "bidirectional"))
    )
    (net (code "61") (name "unconnected-(U2-DB3-Pad10)") (class "Default")
      (node (ref "U2") (pin "10") (pinfunction "DB3_10") (pintype "bidirectional"))
    )
    (net (code "62") (name "unconnected-(U2-LED--Pad16)") (class "Default")
      (node (ref "U2") (pin "16") (pinfunction "LED-_16") (pintype "bidirectional"))
    )
    (net (code "63") (name "unconnected-(U7-NC-Pad8)") (class "Default")
      (node (ref "U7") (pin "8") (pinfunction "NC_8") (pintype "passive"))
    )
    (net (code "64") (name "unconnected-(U7-ON1-Pad1)") (class "Default")
      (node (ref "U7") (pin "1") (pinfunction "ON1_1") (pintype "passive"))
    )
    (net (code "65") (name "unconnected-(U7-ON2-Pad5)") (class "Default")
      (node (ref "U7") (pin "5") (pinfunction "ON2_5") (pintype "passive"))
    )
  )
)
